# vcf3.net
KiCad netlist of a schematic drawn in EAGLE
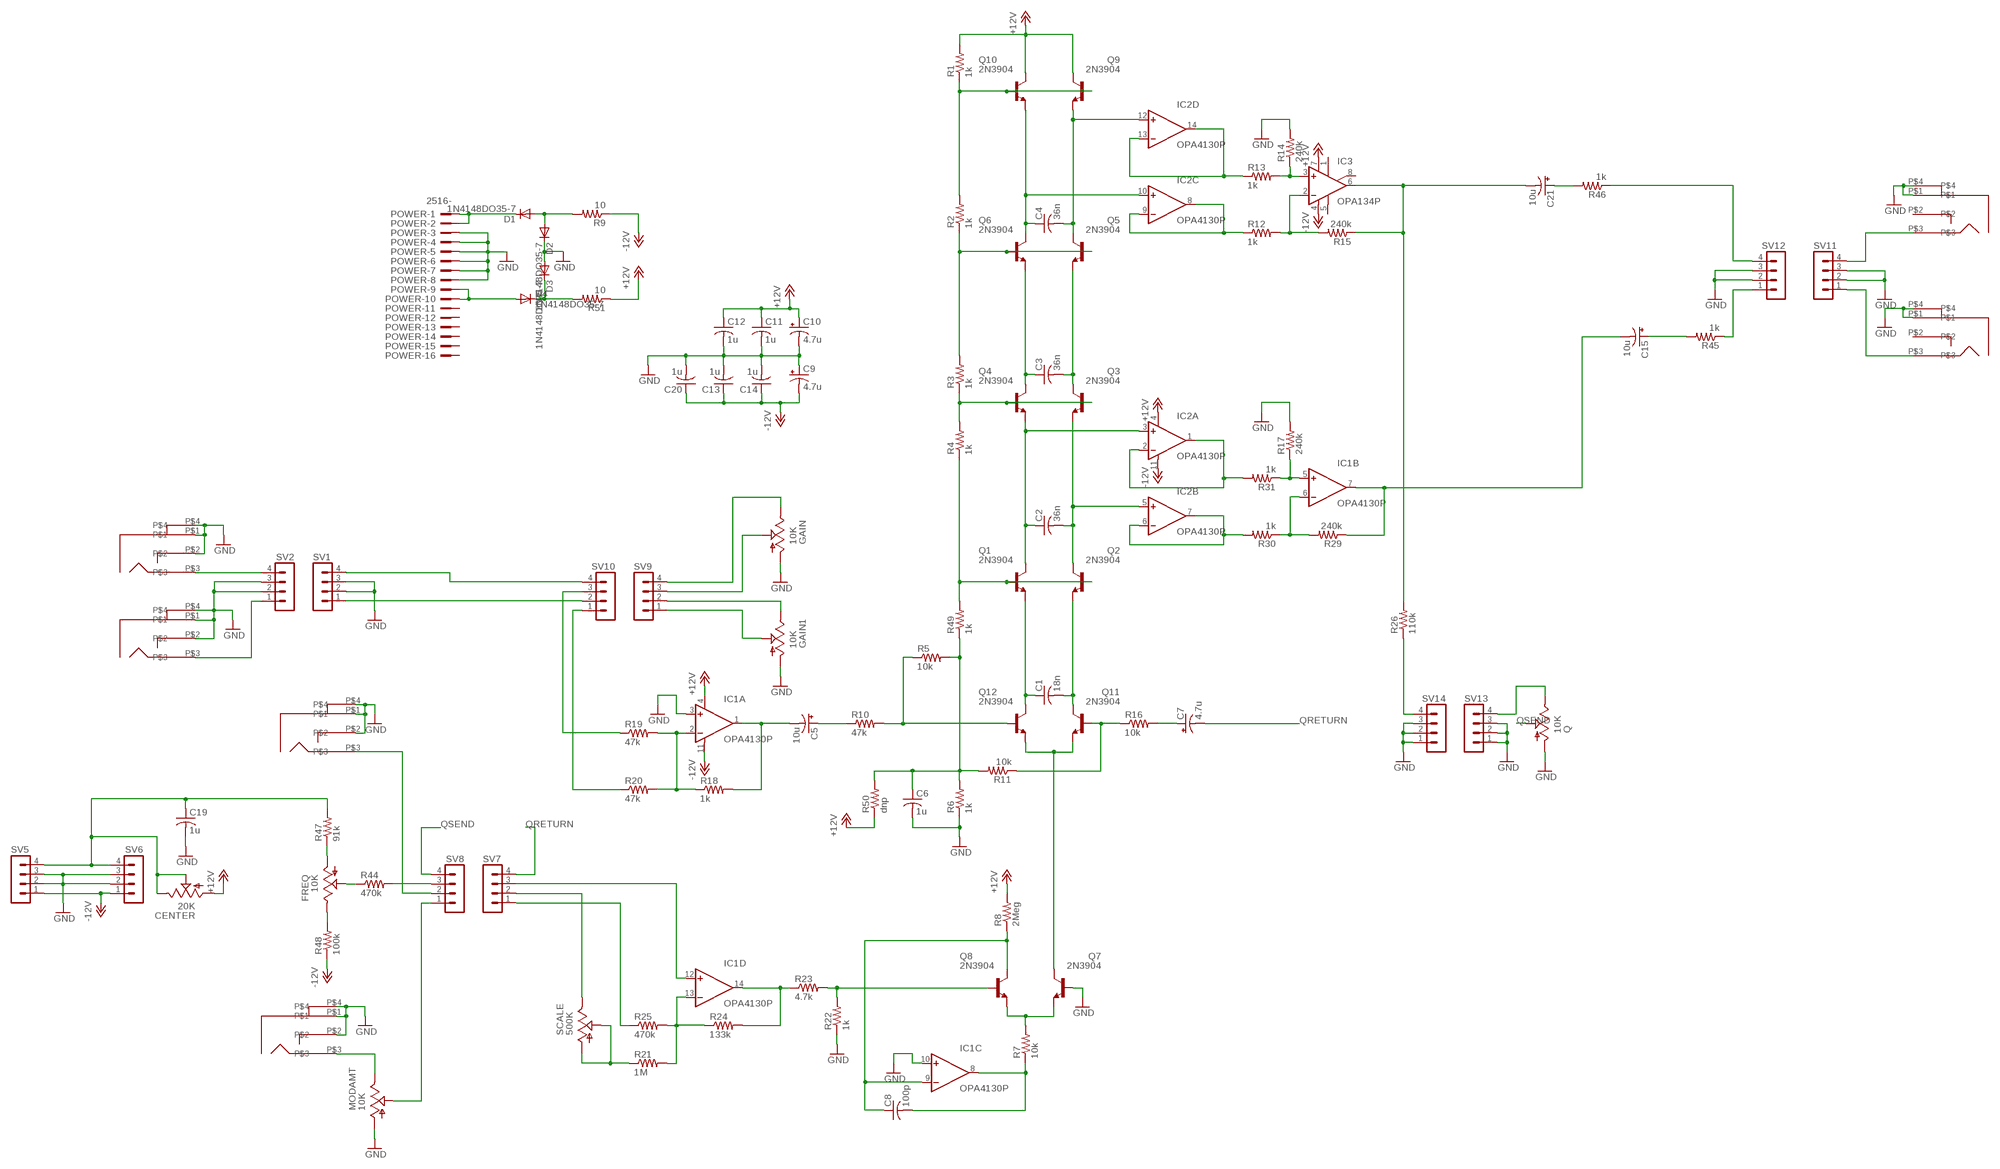
[diagram p0: schematic, sheet 1]

(export (version "E")
  (design (tool "Eeschema 10.0.6"))
  (components
    (comp (ref "AIN")
      (value "PJ301BM")
      (footprint "eagle-import:PJ301BM")
      (libsource (lib "eagle-import") (part "PJ301BM"))
    )
    (comp (ref "AIN2")
      (value "PJ301BM")
      (footprint "eagle-import:PJ301BM")
      (libsource (lib "eagle-import") (part "PJ301BM"))
    )
    (comp (ref "BP")
      (value "PJ301BM")
      (footprint "eagle-import:PJ301BM")
      (libsource (lib "eagle-import") (part "PJ301BM"))
    )
    (comp (ref "C1")
      (value "18n")
      (footprint "eagle-import:C050-025X075")
      (libsource (lib "eagle-import") (part "C-US050-025X075"))
    )
    (comp (ref "C2")
      (value "36n")
      (footprint "eagle-import:C050-025X075")
      (libsource (lib "eagle-import") (part "C-US050-025X075"))
    )
    (comp (ref "C3")
      (value "36n")
      (footprint "eagle-import:C050-025X075")
      (libsource (lib "eagle-import") (part "C-US050-025X075"))
    )
    (comp (ref "C4")
      (value "36n")
      (footprint "eagle-import:C050-025X075")
      (libsource (lib "eagle-import") (part "C-US050-025X075"))
    )
    (comp (ref "C5")
      (value "10u")
      (footprint "eagle-import:E2,5-6")
      (libsource (lib "eagle-import") (part "CPOL-USE2.5-6"))
    )
    (comp (ref "C6")
      (value "1u")
      (footprint "eagle-import:C050-025X075")
      (libsource (lib "eagle-import") (part "C-US050-025X075"))
    )
    (comp (ref "C7")
      (value "4.7u")
      (footprint "eagle-import:E2,5-6")
      (libsource (lib "eagle-import") (part "CPOL-USE2.5-6"))
    )
    (comp (ref "C8")
      (value "100p")
      (footprint "eagle-import:C050-025X075")
      (libsource (lib "eagle-import") (part "C-US050-025X075"))
    )
    (comp (ref "C9")
      (value "4.7u")
      (footprint "eagle-import:E2,5-6")
      (libsource (lib "eagle-import") (part "CPOL-USE2.5-6"))
    )
    (comp (ref "C10")
      (value "4.7u")
      (footprint "eagle-import:E2,5-6")
      (libsource (lib "eagle-import") (part "CPOL-USE2.5-6"))
    )
    (comp (ref "C11")
      (value "1u")
      (footprint "eagle-import:C050-025X075")
      (libsource (lib "eagle-import") (part "C-US050-025X075"))
    )
    (comp (ref "C12")
      (value "1u")
      (footprint "eagle-import:C050-025X075")
      (libsource (lib "eagle-import") (part "C-US050-025X075"))
    )
    (comp (ref "C13")
      (value "1u")
      (footprint "eagle-import:C050-025X075")
      (libsource (lib "eagle-import") (part "C-US050-025X075"))
    )
    (comp (ref "C14")
      (value "1u")
      (footprint "eagle-import:C050-025X075")
      (libsource (lib "eagle-import") (part "C-US050-025X075"))
    )
    (comp (ref "C15")
      (value "10u")
      (footprint "eagle-import:E2,5-6")
      (libsource (lib "eagle-import") (part "CPOL-USE2.5-6"))
    )
    (comp (ref "C19")
      (value "1u")
      (footprint "eagle-import:C050-025X075")
      (libsource (lib "eagle-import") (part "C-US050-025X075"))
    )
    (comp (ref "C20")
      (value "1u")
      (footprint "eagle-import:C050-025X075")
      (libsource (lib "eagle-import") (part "C-US050-025X075"))
    )
    (comp (ref "C21")
      (value "10u")
      (footprint "eagle-import:E2,5-6")
      (libsource (lib "eagle-import") (part "CPOL-USE2.5-6"))
    )
    (comp (ref "CENTER")
      (value "20K")
      (footprint "eagle-import:S64W")
      (libsource (lib "eagle-import") (part "TRIM_US-S64W"))
    )
    (comp (ref "D1")
      (value "1N4148DO35-7")
      (footprint "eagle-import:DO35-7")
      (libsource (lib "eagle-import") (part "1N4148DO35-7"))
    )
    (comp (ref "D2")
      (value "1N4148DO35-7")
      (footprint "eagle-import:DO35-7")
      (libsource (lib "eagle-import") (part "1N4148DO35-7"))
    )
    (comp (ref "D3")
      (value "1N4148DO35-7")
      (footprint "eagle-import:DO35-7")
      (libsource (lib "eagle-import") (part "1N4148DO35-7"))
    )
    (comp (ref "D4")
      (value "1N4148DO35-7")
      (footprint "eagle-import:DO35-7")
      (libsource (lib "eagle-import") (part "1N4148DO35-7"))
    )
    (comp (ref "FREQ")
      (value "10K")
      (footprint "eagle-import:EVUFXJ")
      (libsource (lib "eagle-import") (part "US-EVUF2J"))
    )
    (comp (ref "GAIN")
      (value "10K")
      (footprint "eagle-import:EVUFXJ")
      (libsource (lib "eagle-import") (part "US-EVUF2J"))
    )
    (comp (ref "GAIN1")
      (value "10K")
      (footprint "eagle-import:EVUFXJ")
      (libsource (lib "eagle-import") (part "US-EVUF2J"))
    )
    (comp (ref "IC1")
      (value "OPA4130P")
      (footprint "eagle-import:DIL14")
      (libsource (lib "eagle-import") (part "OPA4130P"))
    )
    (comp (ref "IC2")
      (value "OPA4130P")
      (footprint "eagle-import:DIL14")
      (libsource (lib "eagle-import") (part "OPA4130P"))
    )
    (comp (ref "IC3")
      (value "OPA134P")
      (footprint "eagle-import:DIL08")
      (libsource (lib "eagle-import") (part "OPA134P"))
    )
    (comp (ref "LP")
      (value "PJ301BM")
      (footprint "eagle-import:PJ301BM")
      (libsource (lib "eagle-import") (part "PJ301BM"))
    )
    (comp (ref "MIN")
      (value "PJ301BM")
      (footprint "eagle-import:PJ301BM")
      (libsource (lib "eagle-import") (part "PJ301BM"))
    )
    (comp (ref "MIN1")
      (value "PJ301BM")
      (footprint "eagle-import:PJ301BM")
      (libsource (lib "eagle-import") (part "PJ301BM"))
    )
    (comp (ref "MODAMT")
      (value "10K")
      (footprint "eagle-import:EVUFXJ")
      (libsource (lib "eagle-import") (part "US-EVUF2J"))
    )
    (comp (ref "POWER")
      (value "2516-")
      (footprint "eagle-import:PAK100_2500-16")
      (libsource (lib "eagle-import") (part "2516-"))
    )
    (comp (ref "Q")
      (value "10K")
      (footprint "eagle-import:EVUFXJ")
      (libsource (lib "eagle-import") (part "US-EVUF2J"))
    )
    (comp (ref "Q1")
      (value "2N3904")
      (footprint "eagle-import:TO92")
      (libsource (lib "eagle-import") (part "2N3904"))
    )
    (comp (ref "Q2")
      (value "2N3904")
      (footprint "eagle-import:TO92")
      (libsource (lib "eagle-import") (part "2N3904"))
    )
    (comp (ref "Q3")
      (value "2N3904")
      (footprint "eagle-import:TO92")
      (libsource (lib "eagle-import") (part "2N3904"))
    )
    (comp (ref "Q4")
      (value "2N3904")
      (footprint "eagle-import:TO92")
      (libsource (lib "eagle-import") (part "2N3904"))
    )
    (comp (ref "Q5")
      (value "2N3904")
      (footprint "eagle-import:TO92")
      (libsource (lib "eagle-import") (part "2N3904"))
    )
    (comp (ref "Q6")
      (value "2N3904")
      (footprint "eagle-import:TO92")
      (libsource (lib "eagle-import") (part "2N3904"))
    )
    (comp (ref "Q7")
      (value "2N3904")
      (footprint "eagle-import:TO92")
      (libsource (lib "eagle-import") (part "2N3904"))
    )
    (comp (ref "Q8")
      (value "2N3904")
      (footprint "eagle-import:TO92")
      (libsource (lib "eagle-import") (part "2N3904"))
    )
    (comp (ref "Q9")
      (value "2N3904")
      (footprint "eagle-import:TO92")
      (libsource (lib "eagle-import") (part "2N3904"))
    )
    (comp (ref "Q10")
      (value "2N3904")
      (footprint "eagle-import:TO92")
      (libsource (lib "eagle-import") (part "2N3904"))
    )
    (comp (ref "Q11")
      (value "2N3904")
      (footprint "eagle-import:TO92")
      (libsource (lib "eagle-import") (part "2N3904"))
    )
    (comp (ref "Q12")
      (value "2N3904")
      (footprint "eagle-import:TO92")
      (libsource (lib "eagle-import") (part "2N3904"))
    )
    (comp (ref "R1")
      (value "1k")
      (footprint "eagle-import:0207_2V")
      (libsource (lib "eagle-import") (part "R-US_0207/2V"))
    )
    (comp (ref "R2")
      (value "1k")
      (footprint "eagle-import:0207_2V")
      (libsource (lib "eagle-import") (part "R-US_0207/2V"))
    )
    (comp (ref "R3")
      (value "1k")
      (footprint "eagle-import:0207_2V")
      (libsource (lib "eagle-import") (part "R-US_0207/2V"))
    )
    (comp (ref "R4")
      (value "1k")
      (footprint "eagle-import:0207_2V")
      (libsource (lib "eagle-import") (part "R-US_0207/2V"))
    )
    (comp (ref "R5")
      (value "10k")
      (footprint "eagle-import:0207_2V")
      (libsource (lib "eagle-import") (part "R-US_0207/2V"))
    )
    (comp (ref "R6")
      (value "1k")
      (footprint "eagle-import:0207_2V")
      (libsource (lib "eagle-import") (part "R-US_0207/2V"))
    )
    (comp (ref "R7")
      (value "10k")
      (footprint "eagle-import:0207_2V")
      (libsource (lib "eagle-import") (part "R-US_0207/2V"))
    )
    (comp (ref "R8")
      (value "2Meg")
      (footprint "eagle-import:0207_2V")
      (libsource (lib "eagle-import") (part "R-US_0207/2V"))
    )
    (comp (ref "R9")
      (value "10")
      (footprint "eagle-import:0207_2V")
      (libsource (lib "eagle-import") (part "R-US_0207/2V"))
    )
    (comp (ref "R10")
      (value "47k")
      (footprint "eagle-import:0207_2V")
      (libsource (lib "eagle-import") (part "R-US_0207/2V"))
    )
    (comp (ref "R11")
      (value "10k")
      (footprint "eagle-import:0207_2V")
      (libsource (lib "eagle-import") (part "R-US_0207/2V"))
    )
    (comp (ref "R12")
      (value "1k")
      (footprint "eagle-import:0207_2V")
      (libsource (lib "eagle-import") (part "R-US_0207/2V"))
    )
    (comp (ref "R13")
      (value "1k")
      (footprint "eagle-import:0207_2V")
      (libsource (lib "eagle-import") (part "R-US_0207/2V"))
    )
    (comp (ref "R14")
      (value "240k")
      (footprint "eagle-import:0207_2V")
      (libsource (lib "eagle-import") (part "R-US_0207/2V"))
    )
    (comp (ref "R15")
      (value "240k")
      (footprint "eagle-import:0207_2V")
      (libsource (lib "eagle-import") (part "R-US_0207/2V"))
    )
    (comp (ref "R16")
      (value "10k")
      (footprint "eagle-import:0207_2V")
      (libsource (lib "eagle-import") (part "R-US_0207/2V"))
    )
    (comp (ref "R17")
      (value "240k")
      (footprint "eagle-import:0207_2V")
      (libsource (lib "eagle-import") (part "R-US_0207/2V"))
    )
    (comp (ref "R18")
      (value "1k")
      (footprint "eagle-import:0207_2V")
      (libsource (lib "eagle-import") (part "R-US_0207/2V"))
    )
    (comp (ref "R19")
      (value "47k")
      (footprint "eagle-import:0207_2V")
      (libsource (lib "eagle-import") (part "R-US_0207/2V"))
    )
    (comp (ref "R20")
      (value "47k")
      (footprint "eagle-import:0207_2V")
      (libsource (lib "eagle-import") (part "R-US_0207/2V"))
    )
    (comp (ref "R21")
      (value "1M")
      (footprint "eagle-import:0207_2V")
      (libsource (lib "eagle-import") (part "R-US_0207/2V"))
    )
    (comp (ref "R22")
      (value "1k")
      (footprint "eagle-import:0207_2V")
      (libsource (lib "eagle-import") (part "R-US_0207/2V"))
    )
    (comp (ref "R23")
      (value "4.7k")
      (footprint "eagle-import:0207_2V")
      (libsource (lib "eagle-import") (part "R-US_0207/2V"))
    )
    (comp (ref "R24")
      (value "133k")
      (footprint "eagle-import:0207_2V")
      (libsource (lib "eagle-import") (part "R-US_0207/2V"))
    )
    (comp (ref "R25")
      (value "470k")
      (footprint "eagle-import:0207_2V")
      (libsource (lib "eagle-import") (part "R-US_0207/2V"))
    )
    (comp (ref "R26")
      (value "110k")
      (footprint "eagle-import:0207_2V")
      (libsource (lib "eagle-import") (part "R-US_0207/2V"))
    )
    (comp (ref "R29")
      (value "240k")
      (footprint "eagle-import:0207_2V")
      (libsource (lib "eagle-import") (part "R-US_0207/2V"))
    )
    (comp (ref "R30")
      (value "1k")
      (footprint "eagle-import:0207_2V")
      (libsource (lib "eagle-import") (part "R-US_0207/2V"))
    )
    (comp (ref "R31")
      (value "1k")
      (footprint "eagle-import:0207_2V")
      (libsource (lib "eagle-import") (part "R-US_0207/2V"))
    )
    (comp (ref "R44")
      (value "470k")
      (footprint "eagle-import:0204_7")
      (libsource (lib "eagle-import") (part "R-US_0204/7"))
    )
    (comp (ref "R45")
      (value "1k")
      (footprint "eagle-import:0207_2V")
      (libsource (lib "eagle-import") (part "R-US_0207/2V"))
    )
    (comp (ref "R46")
      (value "1k")
      (footprint "eagle-import:0207_2V")
      (libsource (lib "eagle-import") (part "R-US_0207/2V"))
    )
    (comp (ref "R47")
      (value "91k")
      (footprint "eagle-import:0204_7")
      (libsource (lib "eagle-import") (part "R-US_0204/7"))
    )
    (comp (ref "R48")
      (value "100k")
      (footprint "eagle-import:0204_7")
      (libsource (lib "eagle-import") (part "R-US_0204/7"))
    )
    (comp (ref "R49")
      (value "1k")
      (footprint "eagle-import:0207_2V")
      (libsource (lib "eagle-import") (part "R-US_0207/2V"))
    )
    (comp (ref "R50")
      (value "dnp")
      (footprint "eagle-import:0207_2V")
      (libsource (lib "eagle-import") (part "R-US_0207/2V"))
    )
    (comp (ref "R51")
      (value "10")
      (footprint "eagle-import:0207_2V")
      (libsource (lib "eagle-import") (part "R-US_0207/2V"))
    )
    (comp (ref "SCALE")
      (value "500K")
      (footprint "eagle-import:S64W")
      (libsource (lib "eagle-import") (part "TRIM_US-S64W"))
    )
    (comp (ref "SV1")
      (value "MA04-1")
      (footprint "eagle-import:MA04-1")
      (libsource (lib "eagle-import") (part "MA04-1"))
    )
    (comp (ref "SV2")
      (value "MA04-1")
      (footprint "eagle-import:MA04-1")
      (libsource (lib "eagle-import") (part "MA04-1"))
    )
    (comp (ref "SV5")
      (value "MA04-1")
      (footprint "eagle-import:MA04-1")
      (libsource (lib "eagle-import") (part "MA04-1"))
    )
    (comp (ref "SV6")
      (value "MA04-1")
      (footprint "eagle-import:MA04-1")
      (libsource (lib "eagle-import") (part "MA04-1"))
    )
    (comp (ref "SV7")
      (value "MA04-1")
      (footprint "eagle-import:MA04-1")
      (libsource (lib "eagle-import") (part "MA04-1"))
    )
    (comp (ref "SV8")
      (value "MA04-1")
      (footprint "eagle-import:MA04-1")
      (libsource (lib "eagle-import") (part "MA04-1"))
    )
    (comp (ref "SV9")
      (value "MA04-1")
      (footprint "eagle-import:MA04-1")
      (libsource (lib "eagle-import") (part "MA04-1"))
    )
    (comp (ref "SV10")
      (value "MA04-1")
      (footprint "eagle-import:MA04-1")
      (libsource (lib "eagle-import") (part "MA04-1"))
    )
    (comp (ref "SV11")
      (value "MA04-1")
      (footprint "eagle-import:MA04-1")
      (libsource (lib "eagle-import") (part "MA04-1"))
    )
    (comp (ref "SV12")
      (value "MA04-1")
      (footprint "eagle-import:MA04-1")
      (libsource (lib "eagle-import") (part "MA04-1"))
    )
    (comp (ref "SV13")
      (value "MA04-1")
      (footprint "eagle-import:MA04-1")
      (libsource (lib "eagle-import") (part "MA04-1"))
    )
    (comp (ref "SV14")
      (value "MA04-1")
      (footprint "eagle-import:MA04-1")
      (libsource (lib "eagle-import") (part "MA04-1"))
    )
  )
  (nets
    (net (code "1") (name "+12V") (class "Default")
      (node (ref "C10") (pin "+") (pinfunction "+_+") (pintype "passive"))
      (node (ref "C11") (pin "1") (pinfunction "1_1") (pintype "passive"))
      (node (ref "C12") (pin "1") (pinfunction "1_1") (pintype "passive"))
      (node (ref "CENTER") (pin "A") (pinfunction "A_A") (pintype "passive"))
      (node (ref "IC1") (pin "4") (pinfunction "V+_4") (pintype "power_in"))
      (node (ref "IC2") (pin "4") (pinfunction "V+_4") (pintype "power_in"))
      (node (ref "IC3") (pin "7") (pinfunction "V+_7") (pintype "power_in"))
      (node (ref "Q10") (pin "1") (pinfunction "C_1") (pintype "passive"))
      (node (ref "Q9") (pin "1") (pinfunction "C_1") (pintype "passive"))
      (node (ref "R1") (pin "2") (pinfunction "2_2") (pintype "passive"))
      (node (ref "R50") (pin "1") (pinfunction "1_1") (pintype "passive"))
      (node (ref "R51") (pin "1") (pinfunction "1_1") (pintype "passive"))
      (node (ref "R8") (pin "2") (pinfunction "2_2") (pintype "passive"))
    )
    (net (code "2") (name "-12V") (class "Default")
      (node (ref "C13") (pin "1") (pinfunction "1_1") (pintype "passive"))
      (node (ref "C14") (pin "1") (pinfunction "1_1") (pintype "passive"))
      (node (ref "C20") (pin "1") (pinfunction "1_1") (pintype "passive"))
      (node (ref "C9") (pin "-") (pinfunction "-_-") (pintype "passive"))
      (node (ref "IC1") (pin "11") (pinfunction "V-_11") (pintype "power_in"))
      (node (ref "IC2") (pin "11") (pinfunction "V-_11") (pintype "power_in"))
      (node (ref "IC3") (pin "4") (pinfunction "V-_4") (pintype "power_in"))
      (node (ref "R48") (pin "1") (pinfunction "1_1") (pintype "passive"))
      (node (ref "R9") (pin "1") (pinfunction "1_1") (pintype "passive"))
      (node (ref "SV5") (pin "1") (pinfunction "1_1") (pintype "passive"))
      (node (ref "SV6") (pin "1") (pinfunction "1_1") (pintype "passive"))
    )
    (net (code "3") (name "/QRETURN") (class "Default")
      (node (ref "C7") (pin "-") (pinfunction "-_-") (pintype "passive"))
      (node (ref "SV7") (pin "4") (pinfunction "4_4") (pintype "passive"))
    )
    (net (code "4") (name "/QSEND") (class "Default")
      (node (ref "Q") (pin "2") (pinfunction "S_2") (pintype "passive"))
      (node (ref "SV8") (pin "4") (pinfunction "4_4") (pintype "passive"))
    )
    (net (code "5") (name "GND") (class "Default")
      (node (ref "AIN") (pin "P$1") (pinfunction "P$1_P$1") (pintype "bidirectional"))
      (node (ref "AIN") (pin "P$2") (pinfunction "P$2_P$2") (pintype "bidirectional"))
      (node (ref "AIN") (pin "P$4") (pinfunction "P$4_P$4") (pintype "bidirectional"))
      (node (ref "AIN2") (pin "P$1") (pinfunction "P$1_P$1") (pintype "bidirectional"))
      (node (ref "AIN2") (pin "P$2") (pinfunction "P$2_P$2") (pintype "bidirectional"))
      (node (ref "AIN2") (pin "P$4") (pinfunction "P$4_P$4") (pintype "bidirectional"))
      (node (ref "BP") (pin "P$1") (pinfunction "P$1_P$1") (pintype "bidirectional"))
      (node (ref "BP") (pin "P$4") (pinfunction "P$4_P$4") (pintype "bidirectional"))
      (node (ref "C10") (pin "-") (pinfunction "-_-") (pintype "passive"))
      (node (ref "C11") (pin "2") (pinfunction "2_2") (pintype "passive"))
      (node (ref "C12") (pin "2") (pinfunction "2_2") (pintype "passive"))
      (node (ref "C13") (pin "2") (pinfunction "2_2") (pintype "passive"))
      (node (ref "C14") (pin "2") (pinfunction "2_2") (pintype "passive"))
      (node (ref "C19") (pin "2") (pinfunction "2_2") (pintype "passive"))
      (node (ref "C20") (pin "2") (pinfunction "2_2") (pintype "passive"))
      (node (ref "C6") (pin "2") (pinfunction "2_2") (pintype "passive"))
      (node (ref "C9") (pin "+") (pinfunction "+_+") (pintype "passive"))
      (node (ref "D2") (pin "C") (pinfunction "C_C") (pintype "passive"))
      (node (ref "D3") (pin "A") (pinfunction "A_A") (pintype "passive"))
      (node (ref "GAIN") (pin "1") (pinfunction "A_1") (pintype "passive"))
      (node (ref "GAIN1") (pin "1") (pinfunction "A_1") (pintype "passive"))
      (node (ref "IC1") (pin "10") (pinfunction "+IN_10") (pintype "input"))
      (node (ref "IC1") (pin "3") (pinfunction "+IN_3") (pintype "input"))
      (node (ref "LP") (pin "P$1") (pinfunction "P$1_P$1") (pintype "bidirectional"))
      (node (ref "LP") (pin "P$4") (pinfunction "P$4_P$4") (pintype "bidirectional"))
      (node (ref "MIN") (pin "P$1") (pinfunction "P$1_P$1") (pintype "bidirectional"))
      (node (ref "MIN") (pin "P$2") (pinfunction "P$2_P$2") (pintype "bidirectional"))
      (node (ref "MIN") (pin "P$4") (pinfunction "P$4_P$4") (pintype "bidirectional"))
      (node (ref "MIN1") (pin "P$1") (pinfunction "P$1_P$1") (pintype "bidirectional"))
      (node (ref "MIN1") (pin "P$2") (pinfunction "P$2_P$2") (pintype "bidirectional"))
      (node (ref "MIN1") (pin "P$4") (pinfunction "P$4_P$4") (pintype "bidirectional"))
      (node (ref "MODAMT") (pin "1") (pinfunction "A_1") (pintype "passive"))
      (node (ref "POWER") (pin "3") (pinfunction "KL_3") (pintype "passive"))
      (node (ref "POWER") (pin "4") (pinfunction "KL_4") (pintype "passive"))
      (node (ref "POWER") (pin "5") (pinfunction "KL_5") (pintype "passive"))
      (node (ref "POWER") (pin "6") (pinfunction "KL_6") (pintype "passive"))
      (node (ref "POWER") (pin "7") (pinfunction "KL_7") (pintype "passive"))
      (node (ref "POWER") (pin "8") (pinfunction "KL_8") (pintype "passive"))
      (node (ref "Q") (pin "1") (pinfunction "A_1") (pintype "passive"))
      (node (ref "Q7") (pin "2") (pinfunction "B_2") (pintype "passive"))
      (node (ref "R14") (pin "2") (pinfunction "2_2") (pintype "passive"))
      (node (ref "R17") (pin "2") (pinfunction "2_2") (pintype "passive"))
      (node (ref "R22") (pin "1") (pinfunction "1_1") (pintype "passive"))
      (node (ref "R6") (pin "1") (pinfunction "1_1") (pintype "passive"))
      (node (ref "SV1") (pin "2") (pinfunction "2_2") (pintype "passive"))
      (node (ref "SV1") (pin "3") (pinfunction "3_3") (pintype "passive"))
      (node (ref "SV11") (pin "2") (pinfunction "2_2") (pintype "passive"))
      (node (ref "SV11") (pin "3") (pinfunction "3_3") (pintype "passive"))
      (node (ref "SV12") (pin "2") (pinfunction "2_2") (pintype "passive"))
      (node (ref "SV12") (pin "3") (pinfunction "3_3") (pintype "passive"))
      (node (ref "SV13") (pin "1") (pinfunction "1_1") (pintype "passive"))
      (node (ref "SV13") (pin "2") (pinfunction "2_2") (pintype "passive"))
      (node (ref "SV13") (pin "3") (pinfunction "3_3") (pintype "passive"))
      (node (ref "SV14") (pin "1") (pinfunction "1_1") (pintype "passive"))
      (node (ref "SV14") (pin "2") (pinfunction "2_2") (pintype "passive"))
      (node (ref "SV14") (pin "3") (pinfunction "3_3") (pintype "passive"))
      (node (ref "SV2") (pin "2") (pinfunction "2_2") (pintype "passive"))
      (node (ref "SV2") (pin "3") (pinfunction "3_3") (pintype "passive"))
      (node (ref "SV5") (pin "2") (pinfunction "2_2") (pintype "passive"))
      (node (ref "SV5") (pin "3") (pinfunction "3_3") (pintype "passive"))
      (node (ref "SV6") (pin "2") (pinfunction "2_2") (pintype "passive"))
      (node (ref "SV6") (pin "3") (pinfunction "3_3") (pintype "passive"))
    )
    (net (code "6") (name "Net-(AIN-PadP$3)") (class "Default")
      (node (ref "AIN") (pin "P$3") (pinfunction "P$3_P$3") (pintype "bidirectional"))
      (node (ref "SV2") (pin "4") (pinfunction "4_4") (pintype "passive"))
    )
    (net (code "7") (name "Net-(AIN2-PadP$3)") (class "Default")
      (node (ref "AIN2") (pin "P$3") (pinfunction "P$3_P$3") (pintype "bidirectional"))
      (node (ref "SV2") (pin "1") (pinfunction "1_1") (pintype "passive"))
    )
    (net (code "8") (name "Net-(BP-PadP$3)") (class "Default")
      (node (ref "BP") (pin "P$3") (pinfunction "P$3_P$3") (pintype "bidirectional"))
      (node (ref "SV11") (pin "1") (pinfunction "1_1") (pintype "passive"))
    )
    (net (code "9") (name "Net-(C5-Pad+)") (class "Default")
      (node (ref "C5") (pin "+") (pinfunction "+_+") (pintype "passive"))
      (node (ref "R10") (pin "1") (pinfunction "1_1") (pintype "passive"))
    )
    (net (code "10") (name "Net-(C6-Pad1)") (class "Default")
      (node (ref "C6") (pin "1") (pinfunction "1_1") (pintype "passive"))
      (node (ref "R11") (pin "2") (pinfunction "2_2") (pintype "passive"))
      (node (ref "R49") (pin "1") (pinfunction "1_1") (pintype "passive"))
      (node (ref "R5") (pin "2") (pinfunction "2_2") (pintype "passive"))
      (node (ref "R50") (pin "2") (pinfunction "2_2") (pintype "passive"))
      (node (ref "R6") (pin "2") (pinfunction "2_2") (pintype "passive"))
    )
    (net (code "11") (name "Net-(C7-Pad+)") (class "Default")
      (node (ref "C7") (pin "+") (pinfunction "+_+") (pintype "passive"))
      (node (ref "R16") (pin "2") (pinfunction "2_2") (pintype "passive"))
    )
    (net (code "12") (name "Net-(C15-Pad+)") (class "Default")
      (node (ref "C15") (pin "+") (pinfunction "+_+") (pintype "passive"))
      (node (ref "R45") (pin "2") (pinfunction "2_2") (pintype "passive"))
    )
    (net (code "13") (name "Net-(C19-Pad1)") (class "Default")
      (node (ref "C19") (pin "1") (pinfunction "1_1") (pintype "passive"))
      (node (ref "CENTER") (pin "E") (pinfunction "E_E") (pintype "passive"))
      (node (ref "CENTER") (pin "S") (pinfunction "S_S") (pintype "passive"))
      (node (ref "R47") (pin "2") (pinfunction "2_2") (pintype "passive"))
      (node (ref "SV5") (pin "4") (pinfunction "4_4") (pintype "passive"))
      (node (ref "SV6") (pin "4") (pinfunction "4_4") (pintype "passive"))
    )
    (net (code "14") (name "Net-(C21-Pad+)") (class "Default")
      (node (ref "C21") (pin "+") (pinfunction "+_+") (pintype "passive"))
      (node (ref "R46") (pin "2") (pinfunction "2_2") (pintype "passive"))
    )
    (net (code "15") (name "Net-(D1-PadA)") (class "Default")
      (node (ref "D1") (pin "A") (pinfunction "A_A") (pintype "passive"))
      (node (ref "D2") (pin "A") (pinfunction "A_A") (pintype "passive"))
      (node (ref "R9") (pin "2") (pinfunction "2_2") (pintype "passive"))
    )
    (net (code "16") (name "Net-(D3-PadC)") (class "Default")
      (node (ref "D3") (pin "C") (pinfunction "C_C") (pintype "passive"))
      (node (ref "D4") (pin "C") (pinfunction "C_C") (pintype "passive"))
      (node (ref "R51") (pin "2") (pinfunction "2_2") (pintype "passive"))
    )
    (net (code "17") (name "Net-(FREQ-A)") (class "Default")
      (node (ref "FREQ") (pin "1") (pinfunction "A_1") (pintype "passive"))
      (node (ref "R47") (pin "1") (pinfunction "1_1") (pintype "passive"))
    )
    (net (code "18") (name "Net-(FREQ-E)") (class "Default")
      (node (ref "FREQ") (pin "3") (pinfunction "E_3") (pintype "passive"))
      (node (ref "R48") (pin "2") (pinfunction "2_2") (pintype "passive"))
    )
    (net (code "19") (name "Net-(FREQ-S)") (class "Default")
      (node (ref "FREQ") (pin "2") (pinfunction "S_2") (pintype "passive"))
      (node (ref "R44") (pin "1") (pinfunction "1_1") (pintype "passive"))
    )
    (net (code "20") (name "Net-(GAIN-E)") (class "Default")
      (node (ref "GAIN") (pin "3") (pinfunction "E_3") (pintype "passive"))
      (node (ref "SV9") (pin "4") (pinfunction "4_4") (pintype "passive"))
    )
    (net (code "21") (name "Net-(GAIN-S)") (class "Default")
      (node (ref "GAIN") (pin "2") (pinfunction "S_2") (pintype "passive"))
      (node (ref "SV9") (pin "3") (pinfunction "3_3") (pintype "passive"))
    )
    (net (code "22") (name "Net-(GAIN1-E)") (class "Default")
      (node (ref "GAIN1") (pin "3") (pinfunction "E_3") (pintype "passive"))
      (node (ref "SV9") (pin "2") (pinfunction "2_2") (pintype "passive"))
    )
    (net (code "23") (name "Net-(GAIN1-S)") (class "Default")
      (node (ref "GAIN1") (pin "2") (pinfunction "S_2") (pintype "passive"))
      (node (ref "SV9") (pin "1") (pinfunction "1_1") (pintype "passive"))
    )
    (net (code "24") (name "Net-(IC1A--IN)") (class "Default")
      (node (ref "IC1") (pin "2") (pinfunction "-IN_2") (pintype "input"))
      (node (ref "R18") (pin "1") (pinfunction "1_1") (pintype "passive"))
      (node (ref "R19") (pin "2") (pinfunction "2_2") (pintype "passive"))
      (node (ref "R20") (pin "2") (pinfunction "2_2") (pintype "passive"))
    )
    (net (code "25") (name "Net-(IC1A-OUT)") (class "Default")
      (node (ref "C5") (pin "-") (pinfunction "-_-") (pintype "passive"))
      (node (ref "IC1") (pin "1") (pinfunction "OUT_1") (pintype "output"))
      (node (ref "R18") (pin "2") (pinfunction "2_2") (pintype "passive"))
    )
    (net (code "26") (name "Net-(IC1B-+IN)") (class "Default")
      (node (ref "IC1") (pin "5") (pinfunction "+IN_5") (pintype "input"))
      (node (ref "R17") (pin "1") (pinfunction "1_1") (pintype "passive"))
      (node (ref "R31") (pin "1") (pinfunction "1_1") (pintype "passive"))
    )
    (net (code "27") (name "Net-(IC1B--IN)") (class "Default")
      (node (ref "IC1") (pin "6") (pinfunction "-IN_6") (pintype "input"))
      (node (ref "R29") (pin "2") (pinfunction "2_2") (pintype "passive"))
      (node (ref "R30") (pin "1") (pinfunction "1_1") (pintype "passive"))
    )
    (net (code "28") (name "Net-(IC1B-OUT)") (class "Default")
      (node (ref "C15") (pin "-") (pinfunction "-_-") (pintype "passive"))
      (node (ref "IC1") (pin "7") (pinfunction "OUT_7") (pintype "output"))
      (node (ref "R29") (pin "1") (pinfunction "1_1") (pintype "passive"))
    )
    (net (code "29") (name "Net-(IC1C--IN)") (class "Default")
      (node (ref "C8") (pin "1") (pinfunction "1_1") (pintype "passive"))
      (node (ref "IC1") (pin "9") (pinfunction "-IN_9") (pintype "input"))
      (node (ref "Q8") (pin "1") (pinfunction "C_1") (pintype "passive"))
      (node (ref "R8") (pin "1") (pinfunction "1_1") (pintype "passive"))
    )
    (net (code "30") (name "Net-(IC1C-OUT)") (class "Default")
      (node (ref "C8") (pin "2") (pinfunction "2_2") (pintype "passive"))
      (node (ref "IC1") (pin "8") (pinfunction "OUT_8") (pintype "output"))
      (node (ref "R7") (pin "1") (pinfunction "1_1") (pintype "passive"))
    )
    (net (code "31") (name "Net-(IC1D-+IN)") (class "Default")
      (node (ref "IC1") (pin "12") (pinfunction "+IN_12") (pintype "input"))
      (node (ref "SV7") (pin "3") (pinfunction "3_3") (pintype "passive"))
    )
    (net (code "32") (name "Net-(IC1D--IN)") (class "Default")
      (node (ref "IC1") (pin "13") (pinfunction "-IN_13") (pintype "input"))
      (node (ref "R21") (pin "2") (pinfunction "2_2") (pintype "passive"))
      (node (ref "R24") (pin "1") (pinfunction "1_1") (pintype "passive"))
      (node (ref "R25") (pin "2") (pinfunction "2_2") (pintype "passive"))
    )
    (net (code "33") (name "Net-(IC1D-OUT)") (class "Default")
      (node (ref "IC1") (pin "14") (pinfunction "OUT_14") (pintype "output"))
      (node (ref "R23") (pin "1") (pinfunction "1_1") (pintype "passive"))
      (node (ref "R24") (pin "2") (pinfunction "2_2") (pintype "passive"))
    )
    (net (code "34") (name "Net-(IC2A-+IN)") (class "Default")
      (node (ref "C2") (pin "1") (pinfunction "1_1") (pintype "passive"))
      (node (ref "IC2") (pin "3") (pinfunction "+IN_3") (pintype "input"))
      (node (ref "Q1") (pin "1") (pinfunction "C_1") (pintype "passive"))
      (node (ref "Q4") (pin "3") (pinfunction "E_3") (pintype "passive"))
    )
    (net (code "35") (name "Net-(IC2A--IN)") (class "Default")
      (node (ref "IC2") (pin "1") (pinfunction "OUT_1") (pintype "output"))
      (node (ref "IC2") (pin "2") (pinfunction "-IN_2") (pintype "input"))
      (node (ref "R31") (pin "2") (pinfunction "2_2") (pintype "passive"))
    )
    (net (code "36") (name "Net-(IC2B-+IN)") (class "Default")
      (node (ref "C2") (pin "2") (pinfunction "2_2") (pintype "passive"))
      (node (ref "IC2") (pin "5") (pinfunction "+IN_5") (pintype "input"))
      (node (ref "Q2") (pin "1") (pinfunction "C_1") (pintype "passive"))
      (node (ref "Q3") (pin "3") (pinfunction "E_3") (pintype "passive"))
    )
    (net (code "37") (name "Net-(IC2B--IN)") (class "Default")
      (node (ref "IC2") (pin "6") (pinfunction "-IN_6") (pintype "input"))
      (node (ref "IC2") (pin "7") (pinfunction "OUT_7") (pintype "output"))
      (node (ref "R30") (pin "2") (pinfunction "2_2") (pintype "passive"))
    )
    (net (code "38") (name "Net-(IC2C-+IN)") (class "Default")
      (node (ref "C4") (pin "1") (pinfunction "1_1") (pintype "passive"))
      (node (ref "IC2") (pin "10") (pinfunction "+IN_10") (pintype "input"))
      (node (ref "Q10") (pin "3") (pinfunction "E_3") (pintype "passive"))
      (node (ref "Q6") (pin "1") (pinfunction "C_1") (pintype "passive"))
    )
    (net (code "39") (name "Net-(IC2C--IN)") (class "Default")
      (node (ref "IC2") (pin "8") (pinfunction "OUT_8") (pintype "output"))
      (node (ref "IC2") (pin "9") (pinfunction "-IN_9") (pintype "input"))
      (node (ref "R12") (pin "1") (pinfunction "1_1") (pintype "passive"))
    )
    (net (code "40") (name "Net-(IC2D-+IN)") (class "Default")
      (node (ref "C4") (pin "2") (pinfunction "2_2") (pintype "passive"))
      (node (ref "IC2") (pin "12") (pinfunction "+IN_12") (pintype "input"))
      (node (ref "Q5") (pin "1") (pinfunction "C_1") (pintype "passive"))
      (node (ref "Q9") (pin "3") (pinfunction "E_3") (pintype "passive"))
    )
    (net (code "41") (name "Net-(IC2D--IN)") (class "Default")
      (node (ref "IC2") (pin "13") (pinfunction "-IN_13") (pintype "input"))
      (node (ref "IC2") (pin "14") (pinfunction "OUT_14") (pintype "output"))
      (node (ref "R13") (pin "1") (pinfunction "1_1") (pintype "passive"))
    )
    (net (code "42") (name "Net-(IC3-+IN)") (class "Default")
      (node (ref "IC3") (pin "3") (pinfunction "+IN_3") (pintype "input"))
      (node (ref "R13") (pin "2") (pinfunction "2_2") (pintype "passive"))
      (node (ref "R14") (pin "1") (pinfunction "1_1") (pintype "passive"))
    )
    (net (code "43") (name "Net-(IC3--IN)") (class "Default")
      (node (ref "IC3") (pin "2") (pinfunction "-IN_2") (pintype "input"))
      (node (ref "R12") (pin "2") (pinfunction "2_2") (pintype "passive"))
      (node (ref "R15") (pin "2") (pinfunction "2_2") (pintype "passive"))
    )
    (net (code "44") (name "Net-(IC3-OUT)") (class "Default")
      (node (ref "C21") (pin "-") (pinfunction "-_-") (pintype "passive"))
      (node (ref "IC3") (pin "6") (pinfunction "OUT_6") (pintype "output"))
      (node (ref "R15") (pin "1") (pinfunction "1_1") (pintype "passive"))
      (node (ref "R26") (pin "2") (pinfunction "2_2") (pintype "passive"))
    )
    (net (code "45") (name "Net-(LP-PadP$3)") (class "Default")
      (node (ref "LP") (pin "P$3") (pinfunction "P$3_P$3") (pintype "bidirectional"))
      (node (ref "SV11") (pin "4") (pinfunction "4_4") (pintype "passive"))
    )
    (net (code "46") (name "Net-(MIN1-PadP$3)") (class "Default")
      (node (ref "MIN1") (pin "P$3") (pinfunction "P$3_P$3") (pintype "bidirectional"))
      (node (ref "SV8") (pin "2") (pinfunction "2_2") (pintype "passive"))
    )
    (net (code "47") (name "Net-(MODAMT-E)") (class "Default")
      (node (ref "MIN") (pin "P$3") (pinfunction "P$3_P$3") (pintype "bidirectional"))
      (node (ref "MODAMT") (pin "3") (pinfunction "E_3") (pintype "passive"))
    )
    (net (code "48") (name "Net-(MODAMT-S)") (class "Default")
      (node (ref "MODAMT") (pin "2") (pinfunction "S_2") (pintype "passive"))
      (node (ref "SV8") (pin "1") (pinfunction "1_1") (pintype "passive"))
    )
    (net (code "49") (name "Net-(POWERA-KL)") (class "Default")
      (node (ref "D1") (pin "C") (pinfunction "C_C") (pintype "passive"))
      (node (ref "POWER") (pin "1") (pinfunction "KL_1") (pintype "passive"))
      (node (ref "POWER") (pin "2") (pinfunction "KL_2") (pintype "passive"))
    )
    (net (code "50") (name "Net-(POWERB-KL)") (class "Default")
      (node (ref "D4") (pin "A") (pinfunction "A_A") (pintype "passive"))
      (node (ref "POWER") (pin "10") (pinfunction "KL_10") (pintype "passive"))
      (node (ref "POWER") (pin "9") (pinfunction "KL_9") (pintype "passive"))
    )
    (net (code "51") (name "Net-(Q-E)") (class "Default")
      (node (ref "Q") (pin "3") (pinfunction "E_3") (pintype "passive"))
      (node (ref "SV13") (pin "4") (pinfunction "4_4") (pintype "passive"))
    )
    (net (code "52") (name "Net-(Q1-B)") (class "Default")
      (node (ref "Q1") (pin "2") (pinfunction "B_2") (pintype "passive"))
      (node (ref "Q2") (pin "2") (pinfunction "B_2") (pintype "passive"))
      (node (ref "R4") (pin "1") (pinfunction "1_1") (pintype "passive"))
      (node (ref "R49") (pin "2") (pinfunction "2_2") (pintype "passive"))
    )
    (net (code "53") (name "Net-(Q1-E)") (class "Default")
      (node (ref "C1") (pin "1") (pinfunction "1_1") (pintype "passive"))
      (node (ref "Q1") (pin "3") (pinfunction "E_3") (pintype "passive"))
      (node (ref "Q12") (pin "1") (pinfunction "C_1") (pintype "passive"))
    )
    (net (code "54") (name "Net-(Q3-B)") (class "Default")
      (node (ref "Q3") (pin "2") (pinfunction "B_2") (pintype "passive"))
      (node (ref "Q4") (pin "2") (pinfunction "B_2") (pintype "passive"))
      (node (ref "R3") (pin "1") (pinfunction "1_1") (pintype "passive"))
      (node (ref "R4") (pin "2") (pinfunction "2_2") (pintype "passive"))
    )
    (net (code "55") (name "Net-(Q3-C)") (class "Default")
      (node (ref "C3") (pin "2") (pinfunction "2_2") (pintype "passive"))
      (node (ref "Q3") (pin "1") (pinfunction "C_1") (pintype "passive"))
      (node (ref "Q5") (pin "3") (pinfunction "E_3") (pintype "passive"))
    )
    (net (code "56") (name "Net-(Q4-C)") (class "Default")
      (node (ref "C3") (pin "1") (pinfunction "1_1") (pintype "passive"))
      (node (ref "Q4") (pin "1") (pinfunction "C_1") (pintype "passive"))
      (node (ref "Q6") (pin "3") (pinfunction "E_3") (pintype "passive"))
    )
    (net (code "57") (name "Net-(Q5-B)") (class "Default")
      (node (ref "Q5") (pin "2") (pinfunction "B_2") (pintype "passive"))
      (node (ref "Q6") (pin "2") (pinfunction "B_2") (pintype "passive"))
      (node (ref "R2") (pin "1") (pinfunction "1_1") (pintype "passive"))
      (node (ref "R3") (pin "2") (pinfunction "2_2") (pintype "passive"))
    )
    (net (code "58") (name "Net-(Q7-E)") (class "Default")
      (node (ref "Q7") (pin "3") (pinfunction "E_3") (pintype "passive"))
      (node (ref "Q8") (pin "3") (pinfunction "E_3") (pintype "passive"))
      (node (ref "R7") (pin "2") (pinfunction "2_2") (pintype "passive"))
    )
    (net (code "59") (name "Net-(Q8-B)") (class "Default")
      (node (ref "Q8") (pin "2") (pinfunction "B_2") (pintype "passive"))
      (node (ref "R22") (pin "2") (pinfunction "2_2") (pintype "passive"))
      (node (ref "R23") (pin "2") (pinfunction "2_2") (pintype "passive"))
    )
    (net (code "60") (name "Net-(Q10-B)") (class "Default")
      (node (ref "Q10") (pin "2") (pinfunction "B_2") (pintype "passive"))
      (node (ref "Q9") (pin "2") (pinfunction "B_2") (pintype "passive"))
      (node (ref "R1") (pin "1") (pinfunction "1_1") (pintype "passive"))
      (node (ref "R2") (pin "2") (pinfunction "2_2") (pintype "passive"))
    )
    (net (code "61") (name "Net-(Q11-B)") (class "Default")
      (node (ref "Q11") (pin "2") (pinfunction "B_2") (pintype "passive"))
      (node (ref "R11") (pin "1") (pinfunction "1_1") (pintype "passive"))
      (node (ref "R16") (pin "1") (pinfunction "1_1") (pintype "passive"))
    )
    (net (code "62") (name "Net-(Q11-C)") (class "Default")
      (node (ref "C1") (pin "2") (pinfunction "2_2") (pintype "passive"))
      (node (ref "Q11") (pin "1") (pinfunction "C_1") (pintype "passive"))
      (node (ref "Q2") (pin "3") (pinfunction "E_3") (pintype "passive"))
    )
    (net (code "63") (name "Net-(Q11-E)") (class "Default")
      (node (ref "Q11") (pin "3") (pinfunction "E_3") (pintype "passive"))
      (node (ref "Q12") (pin "3") (pinfunction "E_3") (pintype "passive"))
      (node (ref "Q7") (pin "1") (pinfunction "C_1") (pintype "passive"))
    )
    (net (code "64") (name "Net-(Q12-B)") (class "Default")
      (node (ref "Q12") (pin "2") (pinfunction "B_2") (pintype "passive"))
      (node (ref "R10") (pin "2") (pinfunction "2_2") (pintype "passive"))
      (node (ref "R5") (pin "1") (pinfunction "1_1") (pintype "passive"))
    )
    (net (code "65") (name "Net-(R19-Pad1)") (class "Default")
      (node (ref "R19") (pin "1") (pinfunction "1_1") (pintype "passive"))
      (node (ref "SV10") (pin "3") (pinfunction "3_3") (pintype "passive"))
    )
    (net (code "66") (name "Net-(R20-Pad1)") (class "Default")
      (node (ref "R20") (pin "1") (pinfunction "1_1") (pintype "passive"))
      (node (ref "SV10") (pin "1") (pinfunction "1_1") (pintype "passive"))
    )
    (net (code "67") (name "Net-(R21-Pad1)") (class "Default")
      (node (ref "R21") (pin "1") (pinfunction "1_1") (pintype "passive"))
      (node (ref "SCALE") (pin "A") (pinfunction "A_A") (pintype "passive"))
      (node (ref "SCALE") (pin "S") (pinfunction "S_S") (pintype "passive"))
    )
    (net (code "68") (name "Net-(R25-Pad1)") (class "Default")
      (node (ref "R25") (pin "1") (pinfunction "1_1") (pintype "passive"))
      (node (ref "SV7") (pin "1") (pinfunction "1_1") (pintype "passive"))
    )
    (net (code "69") (name "Net-(R26-Pad1)") (class "Default")
      (node (ref "R26") (pin "1") (pinfunction "1_1") (pintype "passive"))
      (node (ref "SV14") (pin "4") (pinfunction "4_4") (pintype "passive"))
    )
    (net (code "70") (name "Net-(R44-Pad2)") (class "Default")
      (node (ref "R44") (pin "2") (pinfunction "2_2") (pintype "passive"))
      (node (ref "SV8") (pin "3") (pinfunction "3_3") (pintype "passive"))
    )
    (net (code "71") (name "Net-(R45-Pad1)") (class "Default")
      (node (ref "R45") (pin "1") (pinfunction "1_1") (pintype "passive"))
      (node (ref "SV12") (pin "1") (pinfunction "1_1") (pintype "passive"))
    )
    (net (code "72") (name "Net-(R46-Pad1)") (class "Default")
      (node (ref "R46") (pin "1") (pinfunction "1_1") (pintype "passive"))
      (node (ref "SV12") (pin "4") (pinfunction "4_4") (pintype "passive"))
    )
    (net (code "73") (name "Net-(SCALE-PadE)") (class "Default")
      (node (ref "SCALE") (pin "E") (pinfunction "E_E") (pintype "passive"))
      (node (ref "SV7") (pin "2") (pinfunction "2_2") (pintype "passive"))
    )
    (net (code "74") (name "Net-(SV1-Pad1)") (class "Default")
      (node (ref "SV1") (pin "1") (pinfunction "1_1") (pintype "passive"))
      (node (ref "SV10") (pin "2") (pinfunction "2_2") (pintype "passive"))
    )
    (net (code "75") (name "Net-(SV1-Pad4)") (class "Default")
      (node (ref "SV1") (pin "4") (pinfunction "4_4") (pintype "passive"))
      (node (ref "SV10") (pin "4") (pinfunction "4_4") (pintype "passive"))
    )
    (net (code "76") (name "unconnected-(BP-PadP$2)") (class "Default")
      (node (ref "BP") (pin "P$2") (pinfunction "P$2_P$2") (pintype "bidirectional"))
    )
    (net (code "77") (name "unconnected-(IC3-ON1-Pad1)") (class "Default")
      (node (ref "IC3") (pin "1") (pinfunction "ON1_1") (pintype "passive"))
    )
    (net (code "78") (name "unconnected-(IC3-ON2-Pad8)") (class "Default")
      (node (ref "IC3") (pin "8") (pinfunction "ON2_8") (pintype "passive"))
    )
    (net (code "79") (name "unconnected-(IC3-OPT-Pad5)") (class "Default")
      (node (ref "IC3") (pin "5") (pinfunction "OPT_5") (pintype "passive"))
    )
    (net (code "80") (name "unconnected-(LP-PadP$2)") (class "Default")
      (node (ref "LP") (pin "P$2") (pinfunction "P$2_P$2") (pintype "bidirectional"))
    )
    (net (code "81") (name "unconnected-(POWERC-KL-Pad11)") (class "Default")
      (node (ref "POWER") (pin "11") (pinfunction "KL_11") (pintype "passive"))
    )
    (net (code "82") (name "unconnected-(POWERD-KL-Pad12)") (class "Default")
      (node (ref "POWER") (pin "12") (pinfunction "KL_12") (pintype "passive"))
    )
    (net (code "83") (name "unconnected-(POWERE-KL-Pad13)") (class "Default")
      (node (ref "POWER") (pin "13") (pinfunction "KL_13") (pintype "passive"))
    )
    (net (code "84") (name "unconnected-(POWERF-KL-Pad14)") (class "Default")
      (node (ref "POWER") (pin "14") (pinfunction "KL_14") (pintype "passive"))
    )
    (net (code "85") (name "unconnected-(POWERG-KL-Pad15)") (class "Default")
      (node (ref "POWER") (pin "15") (pinfunction "KL_15") (pintype "passive"))
    )
    (net (code "86") (name "unconnected-(POWERH-KL-Pad16)") (class "Default")
      (node (ref "POWER") (pin "16") (pinfunction "KL_16") (pintype "passive"))
    )
  )
)
